# LED_Strip_driver.net
KiCad netlist of a schematic drawn in EAGLE
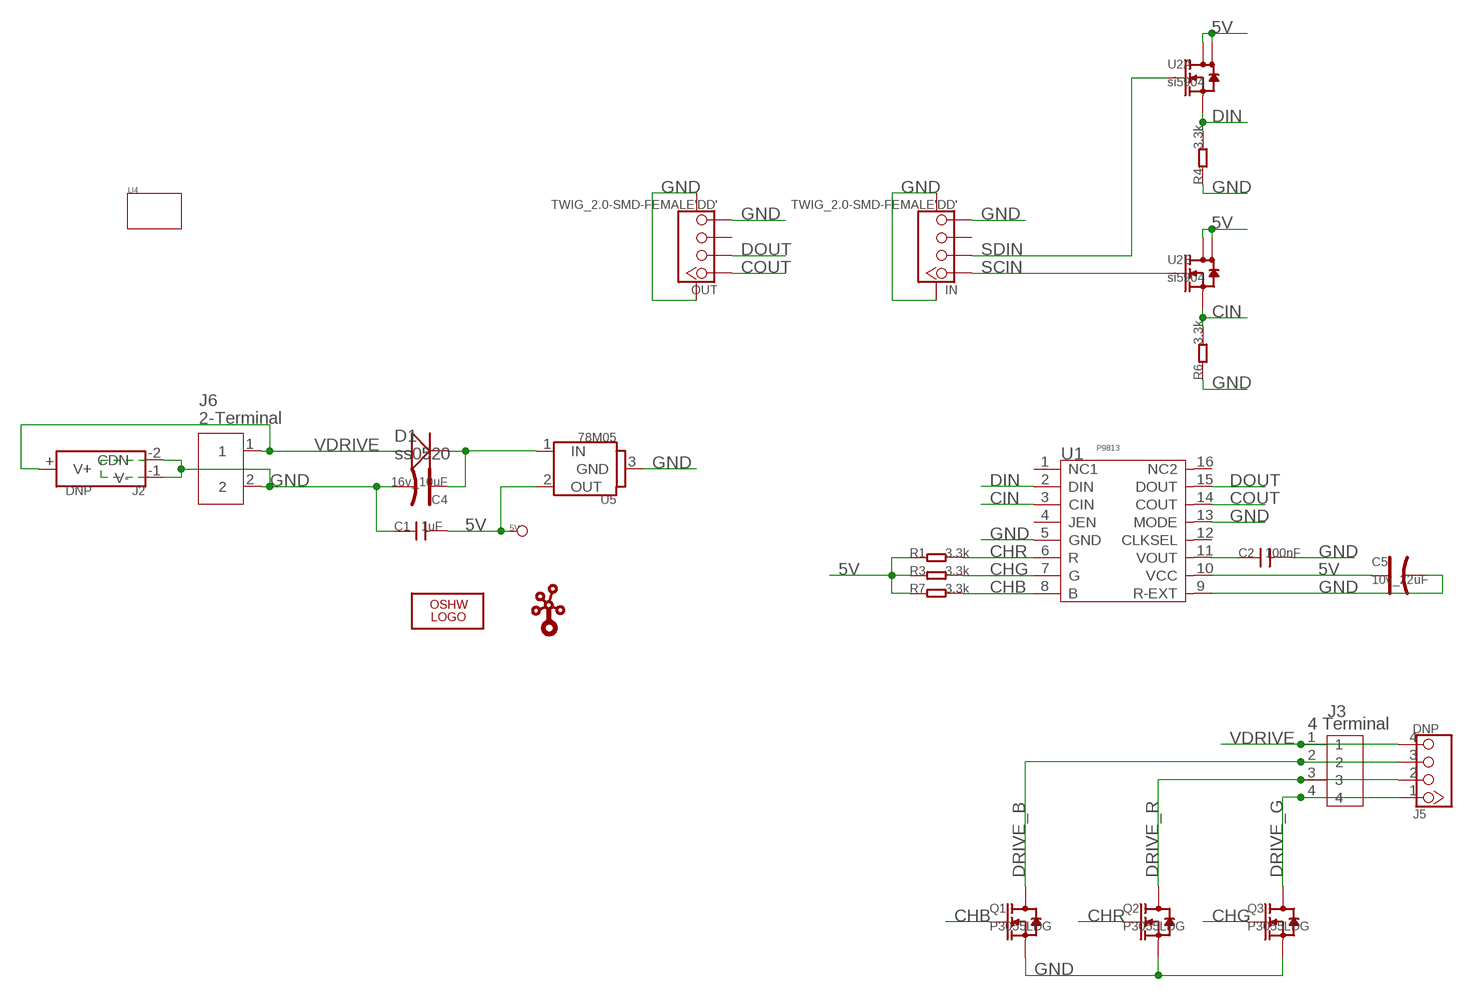
[diagram p0: schematic, sheet 1]

(export (version "E")
  (design (tool "Eeschema 10.0.6"))
  (components
    (comp (ref "5V")
      (value "DNP")
      (footprint "eagle-import:TP_3535")
      (libsource (lib "eagle-import") (part "PAD-TEST-POINT-CIRCLE_SIZE_3030"))
    )
    (comp (ref "C1")
      (value "1uF")
      (footprint "eagle-import:0805")
      (libsource (lib "eagle-import") (part "C-0805"))
    )
    (comp (ref "C2")
      (value "100nF")
      (footprint "eagle-import:0402")
      (libsource (lib "eagle-import") (part "C-0402"))
    )
    (comp (ref "C4")
      (value "16v_10uF")
      (footprint "eagle-import:AVX-A")
      (libsource (lib "eagle-import") (part "CAP-AVX-A"))
    )
    (comp (ref "C5")
      (value "10v_22uF")
      (footprint "eagle-import:AVX-A")
      (libsource (lib "eagle-import") (part "CAP-AVX-A"))
    )
    (comp (ref "D1")
      (value "ss0520")
      (footprint "eagle-import:SOD123")
      (libsource (lib "eagle-import") (part "D'1206'"))
    )
    (comp (ref "IN")
      (value "TWIG_2.0-SMD-FEMALE'DD'")
      (footprint "eagle-import:2.0_1X4DD")
      (libsource (lib "eagle-import") (part "TWIG_2.0-SMD-FEMALE'DD'"))
    )
    (comp (ref "J2")
      (value "DNP")
      (footprint "eagle-import:PW-3P-2.5")
      (libsource (lib "eagle-import") (part "JACK-3P-2.5MM-2.5MM"))
    )
    (comp (ref "J3")
      (value "4 Terminal")
      (footprint "eagle-import:4P-2.54-15.6X12.2X13.2")
      (libsource (lib "eagle-import") (part "SCREW-TERMINAL-4P'2.54'"))
    )
    (comp (ref "J5")
      (value "DNP")
      (footprint "eagle-import:4P-2.54-90")
      (libsource (lib "eagle-import") (part "HEADER-4P-90D"))
    )
    (comp (ref "J6")
      (value "2-Terminal")
      (footprint "eagle-import:2P-2.54-12.1X8.5X13.4")
      (libsource (lib "eagle-import") (part "SCREW-TERMINAL-2P'2.54'"))
    )
    (comp (ref "LOGO1")
      (value "LOGO-OSHW-FILLX0200-NT")
      (footprint "eagle-import:OSHW_FILLX200_NOTEXT")
      (libsource (lib "eagle-import") (part "LOGO-OSHW-FILLX0200-NT"))
    )
    (comp (ref "OUT")
      (value "TWIG_2.0-SMD-FEMALE'DD'")
      (footprint "eagle-import:2.0_1X4DD")
      (libsource (lib "eagle-import") (part "TWIG_2.0-SMD-FEMALE'DD'"))
    )
    (comp (ref "Q1")
      (value "P3055LDG")
      (footprint "eagle-import:TO252")
      (libsource (lib "eagle-import") (part "MOSFET-N-P3055LDG"))
    )
    (comp (ref "Q2")
      (value "P3055LDG")
      (footprint "eagle-import:TO252")
      (libsource (lib "eagle-import") (part "MOSFET-N-P3055LDG"))
    )
    (comp (ref "Q3")
      (value "P3055LDG")
      (footprint "eagle-import:TO252")
      (libsource (lib "eagle-import") (part "MOSFET-N-P3055LDG"))
    )
    (comp (ref "R1")
      (value "3.3k")
      (footprint "eagle-import:0402")
      (libsource (lib "eagle-import") (part "R-0402"))
    )
    (comp (ref "R3")
      (value "3.3k")
      (footprint "eagle-import:0402")
      (libsource (lib "eagle-import") (part "R-0402"))
    )
    (comp (ref "R4")
      (value "3.3k")
      (footprint "eagle-import:0402")
      (libsource (lib "eagle-import") (part "R-0402"))
    )
    (comp (ref "R6")
      (value "3.3k")
      (footprint "eagle-import:0402")
      (libsource (lib "eagle-import") (part "R-0402"))
    )
    (comp (ref "R7")
      (value "3.3k")
      (footprint "eagle-import:0402")
      (libsource (lib "eagle-import") (part "R-0402"))
    )
    (comp (ref "U$1")
      (value "LOGO-TWIG")
      (footprint "eagle-import:TWIGLOGO")
      (libsource (lib "eagle-import") (part "LOGO-TWIG"))
    )
    (comp (ref "U1")
      (value "P9813")
      (footprint "eagle-import:SSOP16")
      (libsource (lib "eagle-import") (part "P9813-SSOP16"))
    )
    (comp (ref "U2")
      (value "si5904")
      (footprint "eagle-import:1206-8")
      (libsource (lib "eagle-import") (part "MOSFET-DUAL-N-1206-8"))
    )
    (comp (ref "U4")
      (value "TWIG3U-W/O-DRILL")
      (footprint "eagle-import:3U-DIM-W_O-DRILL")
      (libsource (lib "eagle-import") (part "TWIG3U-W/O-DRILL"))
    )
    (comp (ref "U5")
      (value "78M05")
      (footprint "eagle-import:TO252")
      (libsource (lib "eagle-import") (part "78M05-TO252"))
    )
  )
  (nets
    (net (code "1") (name "/5V") (class "Default")
      (node (ref "5V") (pin "T") (pinfunction "T_T") (pintype "bidirectional"))
      (node (ref "C1") (pin "2") (pinfunction "2_2") (pintype "passive"))
      (node (ref "C5") (pin "+") (pinfunction "+_+") (pintype "passive"))
      (node (ref "R1") (pin "1") (pinfunction "1_1") (pintype "passive"))
      (node (ref "R3") (pin "1") (pinfunction "1_1") (pintype "passive"))
      (node (ref "R7") (pin "1") (pinfunction "1_1") (pintype "passive"))
      (node (ref "U1") (pin "10") (pinfunction "VCC_10") (pintype "power_in"))
      (node (ref "U2") (pin "5") (pinfunction "D_5") (pintype "passive"))
      (node (ref "U2") (pin "6") (pinfunction "D_6") (pintype "passive"))
      (node (ref "U2") (pin "7") (pinfunction "D_7") (pintype "passive"))
      (node (ref "U2") (pin "8") (pinfunction "D_8") (pintype "passive"))
      (node (ref "U5") (pin "2") (pinfunction "OUT_2") (pintype "bidirectional"))
    )
    (net (code "2") (name "/CHB") (class "Default")
      (node (ref "Q1") (pin "1") (pinfunction "G_1") (pintype "passive"))
      (node (ref "R7") (pin "2") (pinfunction "2_2") (pintype "passive"))
      (node (ref "U1") (pin "8") (pinfunction "B_8") (pintype "output"))
    )
    (net (code "3") (name "/CHG") (class "Default")
      (node (ref "Q3") (pin "1") (pinfunction "G_1") (pintype "passive"))
      (node (ref "R3") (pin "2") (pinfunction "2_2") (pintype "passive"))
      (node (ref "U1") (pin "7") (pinfunction "G_7") (pintype "output"))
    )
    (net (code "4") (name "/CHR") (class "Default")
      (node (ref "Q2") (pin "1") (pinfunction "G_1") (pintype "passive"))
      (node (ref "R1") (pin "2") (pinfunction "2_2") (pintype "passive"))
      (node (ref "U1") (pin "6") (pinfunction "R_6") (pintype "output"))
    )
    (net (code "5") (name "/CIN") (class "Default")
      (node (ref "R6") (pin "2") (pinfunction "2_2") (pintype "passive"))
      (node (ref "U1") (pin "3") (pinfunction "CIN_3") (pintype "input"))
      (node (ref "U2") (pin "3") (pinfunction "S_3") (pintype "passive"))
    )
    (net (code "6") (name "/COUT") (class "Default")
      (node (ref "OUT") (pin "1") (pinfunction "1_1") (pintype "bidirectional"))
      (node (ref "U1") (pin "14") (pinfunction "COUT_14") (pintype "output"))
    )
    (net (code "7") (name "/DIN") (class "Default")
      (node (ref "R4") (pin "2") (pinfunction "2_2") (pintype "passive"))
      (node (ref "U1") (pin "2") (pinfunction "DIN_2") (pintype "input"))
      (node (ref "U2") (pin "1") (pinfunction "S_1") (pintype "passive"))
    )
    (net (code "8") (name "/DOUT") (class "Default")
      (node (ref "OUT") (pin "2") (pinfunction "2_2") (pintype "bidirectional"))
      (node (ref "U1") (pin "15") (pinfunction "DOUT_15") (pintype "output"))
    )
    (net (code "9") (name "/DRIVE_B") (class "Default")
      (node (ref "J3") (pin "2") (pinfunction "2_2") (pintype "bidirectional"))
      (node (ref "J5") (pin "3") (pinfunction "P$3_3") (pintype "bidirectional"))
      (node (ref "Q1") (pin "2") (pinfunction "D_2") (pintype "passive"))
    )
    (net (code "10") (name "/DRIVE_G") (class "Default")
      (node (ref "J3") (pin "4") (pinfunction "4_4") (pintype "bidirectional"))
      (node (ref "J5") (pin "1") (pinfunction "P$1_1") (pintype "bidirectional"))
      (node (ref "Q3") (pin "2") (pinfunction "D_2") (pintype "passive"))
    )
    (net (code "11") (name "/DRIVE_R") (class "Default")
      (node (ref "J3") (pin "3") (pinfunction "3_3") (pintype "bidirectional"))
      (node (ref "J5") (pin "2") (pinfunction "P$2_2") (pintype "bidirectional"))
      (node (ref "Q2") (pin "2") (pinfunction "D_2") (pintype "passive"))
    )
    (net (code "12") (name "/GND") (class "Default")
      (node (ref "C1") (pin "1") (pinfunction "1_1") (pintype "passive"))
      (node (ref "C2") (pin "2") (pinfunction "2_2") (pintype "passive"))
      (node (ref "C4") (pin "-") (pinfunction "-_-") (pintype "passive"))
      (node (ref "C5") (pin "-") (pinfunction "-_-") (pintype "passive"))
      (node (ref "IN") (pin "4") (pinfunction "4_4") (pintype "bidirectional"))
      (node (ref "IN") (pin "SS1") (pinfunction "SS1_SS1") (pintype "bidirectional"))
      (node (ref "IN") (pin "SS2") (pinfunction "SS2_SS2") (pintype "bidirectional"))
      (node (ref "J2") (pin "-1") (pinfunction "V-_-1") (pintype "bidirectional"))
      (node (ref "J2") (pin "-2") (pinfunction "CDN_-2") (pintype "bidirectional"))
      (node (ref "J6") (pin "2") (pinfunction "2_2") (pintype "bidirectional"))
      (node (ref "OUT") (pin "4") (pinfunction "4_4") (pintype "bidirectional"))
      (node (ref "OUT") (pin "SS1") (pinfunction "SS1_SS1") (pintype "bidirectional"))
      (node (ref "OUT") (pin "SS2") (pinfunction "SS2_SS2") (pintype "bidirectional"))
      (node (ref "Q1") (pin "3") (pinfunction "S_3") (pintype "passive"))
      (node (ref "Q2") (pin "3") (pinfunction "S_3") (pintype "passive"))
      (node (ref "Q3") (pin "3") (pinfunction "S_3") (pintype "passive"))
      (node (ref "R4") (pin "1") (pinfunction "1_1") (pintype "passive"))
      (node (ref "R6") (pin "1") (pinfunction "1_1") (pintype "passive"))
      (node (ref "U1") (pin "13") (pinfunction "MODE_13") (pintype "input"))
      (node (ref "U1") (pin "5") (pinfunction "GND_5") (pintype "power_in"))
      (node (ref "U1") (pin "9") (pinfunction "R-EXT_9") (pintype "input"))
      (node (ref "U5") (pin "3") (pinfunction "GND_3") (pintype "bidirectional"))
    )
    (net (code "13") (name "/SCIN") (class "Default")
      (node (ref "IN") (pin "1") (pinfunction "1_1") (pintype "bidirectional"))
      (node (ref "U2") (pin "4") (pinfunction "G_4") (pintype "passive"))
    )
    (net (code "14") (name "/SDIN") (class "Default")
      (node (ref "IN") (pin "2") (pinfunction "2_2") (pintype "bidirectional"))
      (node (ref "U2") (pin "2") (pinfunction "G_2") (pintype "passive"))
    )
    (net (code "15") (name "/VDRIVE") (class "Default")
      (node (ref "D1") (pin "+") (pinfunction "+_+") (pintype "passive"))
      (node (ref "J2") (pin "+") (pinfunction "V+_+") (pintype "bidirectional"))
      (node (ref "J3") (pin "1") (pinfunction "1_1") (pintype "bidirectional"))
      (node (ref "J5") (pin "4") (pinfunction "P$4_4") (pintype "bidirectional"))
      (node (ref "J6") (pin "1") (pinfunction "1_1") (pintype "bidirectional"))
    )
    (net (code "16") (name "Net-(U1-VOUT)") (class "Default")
      (node (ref "C2") (pin "1") (pinfunction "1_1") (pintype "passive"))
      (node (ref "U1") (pin "11") (pinfunction "VOUT_11") (pintype "output"))
    )
    (net (code "17") (name "Net-(U5-IN)") (class "Default")
      (node (ref "C4") (pin "+") (pinfunction "+_+") (pintype "passive"))
      (node (ref "D1") (pin "-") (pinfunction "-_-") (pintype "passive"))
      (node (ref "U5") (pin "1") (pinfunction "IN_1") (pintype "bidirectional"))
    )
    (net (code "18") (name "unconnected-(IN-Pad3)") (class "Default")
      (node (ref "IN") (pin "3") (pinfunction "3_3") (pintype "bidirectional"))
    )
    (net (code "19") (name "unconnected-(OUT-Pad3)") (class "Default")
      (node (ref "OUT") (pin "3") (pinfunction "3_3") (pintype "bidirectional"))
    )
    (net (code "20") (name "unconnected-(U1-CLKSEL-Pad12)") (class "Default")
      (node (ref "U1") (pin "12") (pinfunction "CLKSEL_12") (pintype "input"))
    )
    (net (code "21") (name "unconnected-(U1-JEN-Pad4)") (class "Default")
      (node (ref "U1") (pin "4") (pinfunction "JEN_4") (pintype "input"))
    )
    (net (code "22") (name "unconnected-(U1-NC1-Pad1)") (class "Default")
      (node (ref "U1") (pin "1") (pinfunction "NC1_1") (pintype "no_connect"))
    )
    (net (code "23") (name "unconnected-(U1-NC2-Pad16)") (class "Default")
      (node (ref "U1") (pin "16") (pinfunction "NC2_16") (pintype "no_connect"))
    )
  )
)
